# GSM_Power.net
KiCad netlist of a schematic drawn in Altium Designer
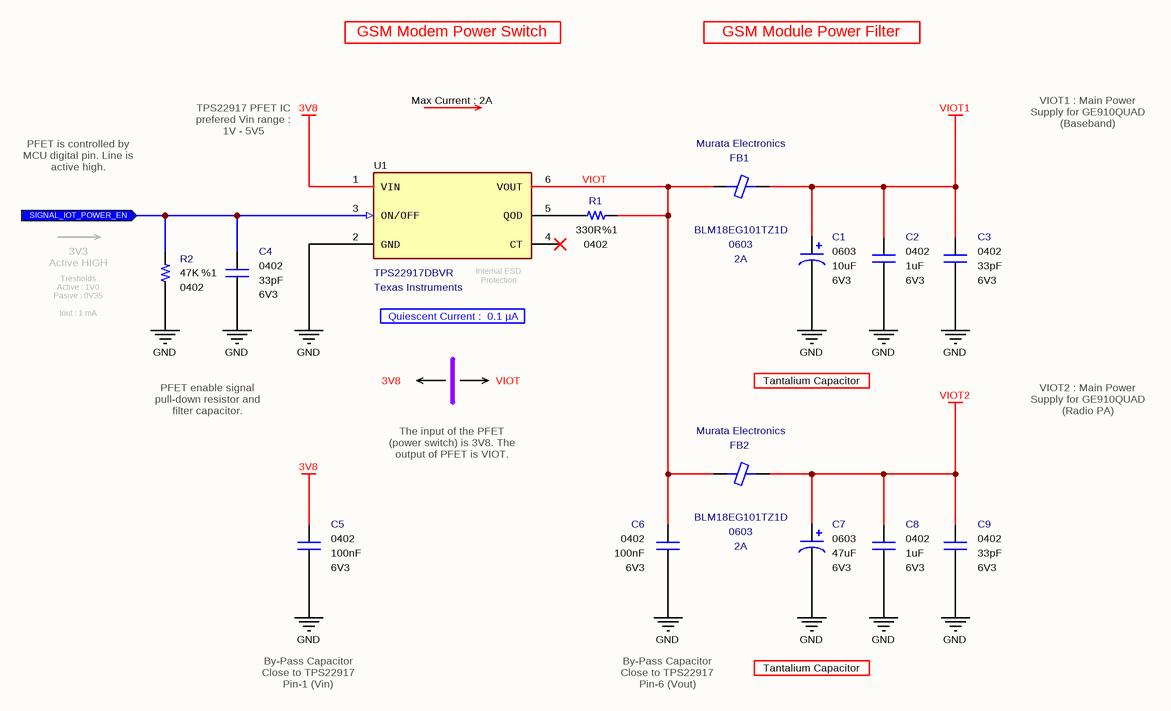
[diagram p0: GSM Power.SchDoc]

(export (version "E")
  (design (tool "Eeschema 10.0.6"))
  (components
    (comp (ref "C1")
      (value "10uF")
      (footprint "CAPACITOR_0603 - TANTALUM")
      (description "Capacitor - 10uF [0603] (Tantalium)")
      (fields
        (field (name "TOLERANCE") "20%")
        (field (name "CASE") "0603")
        (field (name "VOLTAGE") "6V3")
        (field (name "MANUFACTURER PART NUMBER") "F380J106MMAAH3")
      )
      (libsource (lib "Ovoo_Library") (part "Capacitor - 10uF [0603-6V3] (Tantalium)"))
    )
    (comp (ref "C2")
      (value "1uF")
      (footprint "CAPACITOR_0402")
      (description "Capacitor - 1uF [0402] (Ceramic)")
      (fields
        (field (name "TOLERANCE") "20%")
        (field (name "CASE") "0402")
        (field (name "VOLTAGE") "6V3")
        (field (name "MANUFACTURER PART NUMBER") "GRM153R60J105ME95D")
      )
      (libsource (lib "Ovoo_Library") (part "Capacitor - 1uF [0402-6V3]"))
    )
    (comp (ref "C3")
      (value "33pF")
      (footprint "CAPACITOR_0402")
      (description "Capacitor - 33pF [0402] (Ceramic)")
      (fields
        (field (name "TOLERANCE") "10%")
        (field (name "CASE") "0402")
        (field (name "VOLTAGE") "6V3")
        (field (name "MANUFACTURER PART NUMBER") "C0402C330J9RACAUTO")
      )
      (libsource (lib "Ovoo_Library") (part "Capacitor - 33pF [0402-6V3]"))
    )
    (comp (ref "C4")
      (value "33pF")
      (footprint "CAPACITOR_0402")
      (description "Capacitor - 33pF [0402] (Ceramic)")
      (fields
        (field (name "TOLERANCE") "10%")
        (field (name "CASE") "0402")
        (field (name "VOLTAGE") "6V3")
        (field (name "MANUFACTURER PART NUMBER") "C0402C330J9RACAUTO")
      )
      (libsource (lib "Ovoo_Library") (part "Capacitor - 33pF [0402-6V3]"))
    )
    (comp (ref "C5")
      (value "100nF")
      (footprint "CAPACITOR_0402")
      (description "Capacitor - 100nF [0402-6V3] (Ceramic)")
      (fields
        (field (name "CASE") "0402")
        (field (name "TOLERANCE") "%10")
        (field (name "VOLTAGE") "6V3")
        (field (name "MANUFACTURER PART NUMBER") "04026D104KAT4A")
      )
      (libsource (lib "Ovoo_Library") (part "Capacitor - 100nF [0402-6V3]"))
    )
    (comp (ref "C6")
      (value "100nF")
      (footprint "CAPACITOR_0402")
      (description "Capacitor - 100nF [0402-6V3] (Ceramic)")
      (fields
        (field (name "CASE") "0402")
        (field (name "TOLERANCE") "%10")
        (field (name "VOLTAGE") "6V3")
        (field (name "MANUFACTURER PART NUMBER") "04026D104KAT4A")
      )
      (libsource (lib "Ovoo_Library") (part "Capacitor - 100nF [0402-6V3]"))
    )
    (comp (ref "C7")
      (value "47uF")
      (footprint "CAPACITOR_0603 - TANTALUM")
      (description "Capacitor - 47uF [0603] (Tantalium)")
      (fields
        (field (name "TOLERANCE") "20%")
        (field (name "CASE") "0603")
        (field (name "VOLTAGE") "6V3")
        (field (name "MANUFACTURER PART NUMBER") "F380J476MMAAXEH3")
      )
      (libsource (lib "Ovoo_Library") (part "Capacitor - 47u [0603-6V3] (Tantalium)"))
    )
    (comp (ref "C8")
      (value "1uF")
      (footprint "CAPACITOR_0402")
      (description "Capacitor - 1uF [0402] (Ceramic)")
      (fields
        (field (name "TOLERANCE") "20%")
        (field (name "CASE") "0402")
        (field (name "VOLTAGE") "6V3")
        (field (name "MANUFACTURER PART NUMBER") "GRM153R60J105ME95D")
      )
      (libsource (lib "Ovoo_Library") (part "Capacitor - 1uF [0402-6V3]"))
    )
    (comp (ref "C9")
      (value "33pF")
      (footprint "CAPACITOR_0402")
      (description "Capacitor - 33pF [0402] (Ceramic)")
      (fields
        (field (name "TOLERANCE") "10%")
        (field (name "CASE") "0402")
        (field (name "VOLTAGE") "6V3")
        (field (name "MANUFACTURER PART NUMBER") "C0402C330J9RACAUTO")
      )
      (libsource (lib "Ovoo_Library") (part "Capacitor - 33pF [0402-6V3]"))
    )
    (comp (ref "FB1")
      (value "BLM18EG101TZ1D")
      (footprint "INDUCATOR_0603")
      (description "Ferrite Beads 0603 100ohms 2000mA Auto Infotainment")
      (fields
        (field (name "TOLERANCE") "25%")
        (field (name "CASE") "0603")
        (field (name "MAXIMUM DC CURRENT") "2A")
        (field (name "MOUSER PART NUMBER") "81-BLM18EG101TZ1D")
        (field (name "MANUFACTURER NAME") "Murata Electronics")
      )
      (libsource (lib "Ovoo_Library") (part "Ferrite Bead - 2A [0603]"))
    )
    (comp (ref "FB2")
      (value "BLM18EG101TZ1D")
      (footprint "INDUCATOR_0603")
      (description "Ferrite Beads 0603 100ohms 2000mA Auto Infotainment")
      (fields
        (field (name "TOLERANCE") "25%")
        (field (name "CASE") "0603")
        (field (name "MAXIMUM DC CURRENT") "2A")
        (field (name "MOUSER PART NUMBER") "81-BLM18EG101TZ1D")
        (field (name "MANUFACTURER NAME") "Murata Electronics")
      )
      (libsource (lib "Ovoo_Library") (part "Ferrite Bead - 2A [0603]"))
    )
    (comp (ref "R1")
      (value "330R")
      (footprint "RESISTOR_0402")
      (description "Thick Film Resistors - SMD 1/16 W 330 Ohm 1%")
      (fields
        (field (name "TOLERANCE") "%1")
        (field (name "CASE") "0402")
        (field (name "MANUFACTURER PART NUMBER") "CRCW0402330RFKED")
        (field (name "MOUSER PART NUMBER") "71-CRCW0402-330-E3")
      )
      (libsource (lib "Ovoo_Library") (part "Resistor - 330R"))
    )
    (comp (ref "R2")
      (value "47K")
      (footprint "RESISTOR_0402")
      (description "Thick Film Resistors - SMD 1/16 W 47 Kohms 1%")
      (fields
        (field (name "TOLERANCE") "%1")
        (field (name "CASE") "0402")
        (field (name "MANUFACTURER PART NUMBER") "CRCW040247K0FKED")
        (field (name "MOUSER PART NUMBER") "71-CRCW0402-47K-E3")
      )
      (libsource (lib "Ovoo_Library") (part "Resistor - 47K"))
    )
    (comp (ref "U1")
      (value "Power Switch")
      (footprint "SOT-23-6")
      (description "Power Switch MosFet")
      (fields
        (field (name "MOUSER PART NUMBER") "595-TPS22917DBVR")
        (field (name "MANUFACTURER PART NUMBER") "TPS22917DBVR")
        (field (name "MANUFACTURER NAME") "Texas Instruments")
      )
      (libsource (lib "Ovoo_Library") (part "IC - TPS22917DBVR"))
    )
  )
  (nets
    (net (code "1") (name "/SIGNAL_IOT_POWER_EN") (class "Default")
      (node (ref "C4") (pin "2") (pinfunction "2_2") (pintype "passive"))
      (node (ref "R2") (pin "2") (pinfunction "2_2") (pintype "passive"))
      (node (ref "U1") (pin "3") (pinfunction "ON/OFF_3") (pintype "input"))
    )
    (net (code "2") (name "/VIOT") (class "Default")
      (node (ref "C6") (pin "1") (pinfunction "1_1") (pintype "passive"))
      (node (ref "FB1") (pin "1") (pinfunction "1_1") (pintype "passive"))
      (node (ref "FB2") (pin "1") (pinfunction "1_1") (pintype "passive"))
      (node (ref "R1") (pin "1") (pinfunction "1_1") (pintype "passive"))
      (node (ref "U1") (pin "6") (pinfunction "VOUT_6") (pintype "power_in"))
    )
    (net (code "3") (name "3V8") (class "Default")
      (node (ref "C5") (pin "1") (pinfunction "1_1") (pintype "passive"))
      (node (ref "U1") (pin "1") (pinfunction "VIN_1") (pintype "power_in"))
    )
    (net (code "4") (name "GND") (class "Default")
      (node (ref "C1") (pin "2") (pinfunction "2_2") (pintype "passive"))
      (node (ref "C2") (pin "1") (pinfunction "1_1") (pintype "passive"))
      (node (ref "C3") (pin "1") (pinfunction "1_1") (pintype "passive"))
      (node (ref "C4") (pin "1") (pinfunction "1_1") (pintype "passive"))
      (node (ref "C5") (pin "2") (pinfunction "2_2") (pintype "passive"))
      (node (ref "C6") (pin "2") (pinfunction "2_2") (pintype "passive"))
      (node (ref "C7") (pin "2") (pinfunction "2_2") (pintype "passive"))
      (node (ref "C8") (pin "1") (pinfunction "1_1") (pintype "passive"))
      (node (ref "C9") (pin "1") (pinfunction "1_1") (pintype "passive"))
      (node (ref "R2") (pin "1") (pinfunction "1_1") (pintype "passive"))
      (node (ref "U1") (pin "2") (pinfunction "GND_2") (pintype "power_in"))
    )
    (net (code "5") (name "Net-(U1-QOD)") (class "Default")
      (node (ref "R1") (pin "2") (pinfunction "2_2") (pintype "passive"))
      (node (ref "U1") (pin "5") (pinfunction "QOD_5") (pintype "power_in"))
    )
    (net (code "6") (name "VIOT1") (class "Default")
      (node (ref "C1") (pin "1") (pinfunction "1_1") (pintype "passive"))
      (node (ref "C2") (pin "2") (pinfunction "2_2") (pintype "passive"))
      (node (ref "C3") (pin "2") (pinfunction "2_2") (pintype "passive"))
      (node (ref "FB1") (pin "2") (pinfunction "2_2") (pintype "passive"))
    )
    (net (code "7") (name "VIOT2") (class "Default")
      (node (ref "C7") (pin "1") (pinfunction "1_1") (pintype "passive"))
      (node (ref "C8") (pin "2") (pinfunction "2_2") (pintype "passive"))
      (node (ref "C9") (pin "2") (pinfunction "2_2") (pintype "passive"))
      (node (ref "FB2") (pin "2") (pinfunction "2_2") (pintype "passive"))
    )
    (net (code "8") (name "unconnected-(U1-CT-Pad4)") (class "Default")
      (node (ref "U1") (pin "4") (pinfunction "CT_4") (pintype "power_in+no_connect"))
    )
  )
)
